# magnes.net
KiCad netlist of a schematic drawn in EAGLE
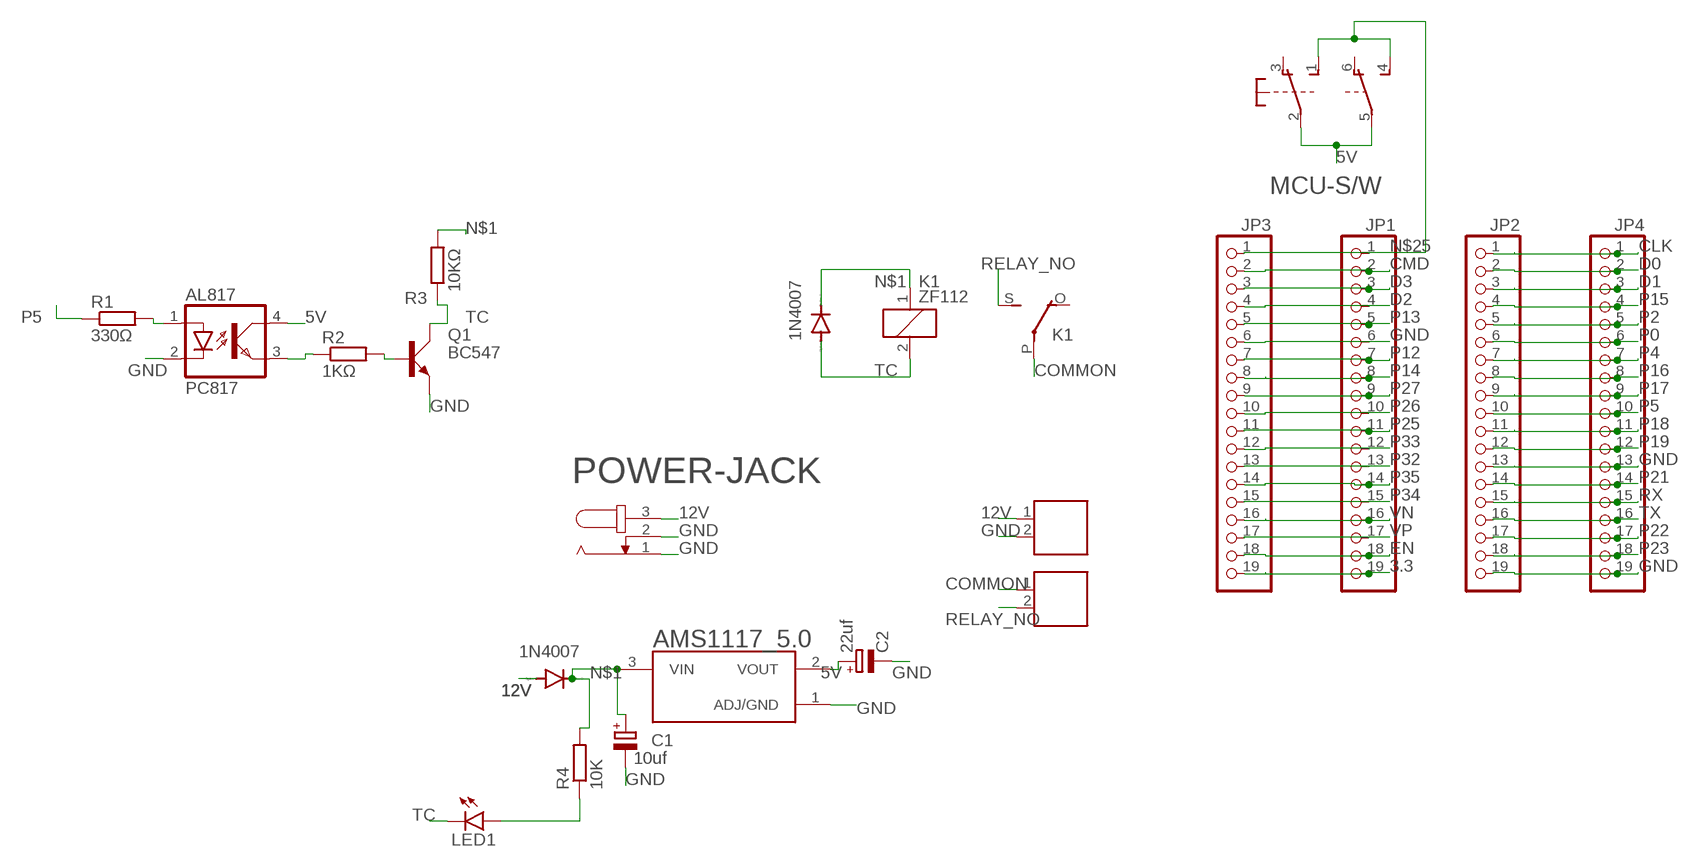
[diagram p0: schematic, sheet 1]

(export (version "E")
  (design (tool "Eeschema 10.0.6"))
  (components
    (comp (ref "1N1")
      (value "1N4007")
      (footprint "eagle-import:D-7.5")
      (libsource (lib "eagle-import") (part "DIODE-D-7.5"))
    )
    (comp (ref "1N4007")
      (value "DIODE-D-7.5")
      (footprint "eagle-import:D-7.5")
      (libsource (lib "eagle-import") (part "DIODE-D-7.5"))
    )
    (comp (ref "AL817")
      (value "PC817")
      (footprint "eagle-import:DIL04")
      (fields (field (name "MPN") "PC817X4J000F"))
      (libsource (lib "eagle-import") (part "PC817"))
    )
    (comp (ref "AMS1117_5.0")
      (value "AMS1117-3.3")
      (footprint "eagle-import:SOT229P700X180-4N")
      (fields (field (name "MF") "Advanced Monolithic Systems"))
      (libsource (lib "eagle-import") (part "AMS1117-3.3"))
    )
    (comp (ref "C1")
      (value "10uf")
      (footprint "eagle-import:E2,5-6")
      (libsource (lib "eagle-import") (part "CPOL-EUE2.5-6"))
    )
    (comp (ref "C2")
      (value "22uf")
      (footprint "eagle-import:E2,5-6")
      (libsource (lib "eagle-import") (part "CPOL-EUE2.5-6"))
    )
    (comp (ref "JP1")
      (value "PINHD-1X19")
      (footprint "eagle-import:1X19")
      (libsource (lib "eagle-import") (part "PINHD-1X19"))
    )
    (comp (ref "JP2")
      (value "PINHD-1X19")
      (footprint "eagle-import:1X19")
      (libsource (lib "eagle-import") (part "PINHD-1X19"))
    )
    (comp (ref "JP3")
      (value "PINHD-1X19")
      (footprint "eagle-import:1X19")
      (libsource (lib "eagle-import") (part "PINHD-1X19"))
    )
    (comp (ref "JP4")
      (value "PINHD-1X19")
      (footprint "eagle-import:1X19")
      (libsource (lib "eagle-import") (part "PINHD-1X19"))
    )
    (comp (ref "K1")
      (value "ZF112")
      (footprint "eagle-import:ZF112")
      (libsource (lib "eagle-import") (part "ZF112"))
    )
    (comp (ref "LED1")
      (value "LED3MM")
      (footprint "eagle-import:LED3MM")
      (libsource (lib "eagle-import") (part "LED3MM"))
    )
    (comp (ref "MCU-S/W")
      (value "9077-2")
      (footprint "eagle-import:9077-2")
      (libsource (lib "eagle-import") (part "9077-2"))
    )
    (comp (ref "PCBSCREWTERMINAL")
      (value "691131710002")
      (footprint "eagle-import:691131710002")
      (libsource (lib "eagle-import") (part "691131710002"))
    )
    (comp (ref "PCBSCREWTERMINAL1")
      (value "691131710002")
      (footprint "eagle-import:691131710002")
      (libsource (lib "eagle-import") (part "691131710002"))
    )
    (comp (ref "POWER-JACK")
      (value "JACK-PLUG1")
      (footprint "eagle-import:SPC4078")
      (libsource (lib "eagle-import") (part "JACK-PLUG1"))
    )
    (comp (ref "Q1")
      (value "BC547")
      (footprint "eagle-import:SOT54A")
      (libsource (lib "eagle-import") (part "BC547"))
    )
    (comp (ref "R1")
      (value "330Ω")
      (footprint "eagle-import:0204_7")
      (libsource (lib "eagle-import") (part "R-EU_0204/7"))
    )
    (comp (ref "R2")
      (value "1KΩ")
      (footprint "eagle-import:0204_7")
      (libsource (lib "eagle-import") (part "R-EU_0204/7"))
    )
    (comp (ref "R3")
      (value "10KΩ")
      (footprint "eagle-import:0204_7")
      (libsource (lib "eagle-import") (part "R-EU_0204/7"))
    )
    (comp (ref "R4")
      (value "10K")
      (footprint "eagle-import:0204_7")
      (libsource (lib "eagle-import") (part "R-EU_0204/7"))
    )
  )
  (nets
    (net (code "1") (name "/3.3") (class "Default")
      (node (ref "JP1") (pin "19") (pinfunction "19_19") (pintype "passive"))
      (node (ref "JP3") (pin "19") (pinfunction "19_19") (pintype "passive"))
    )
    (net (code "2") (name "/5V") (class "Default")
      (node (ref "AL817") (pin "4") (pinfunction "COL_4") (pintype "passive"))
      (node (ref "AMS1117_5.0") (pin "2") (pinfunction "VOUT_2") (pintype "output"))
      (node (ref "C2") (pin "+") (pinfunction "+_+") (pintype "passive"))
      (node (ref "MCU-S/W") (pin "2") (pinfunction "P_2") (pintype "passive"))
      (node (ref "MCU-S/W") (pin "5") (pinfunction "P_5") (pintype "passive"))
    )
    (net (code "3") (name "/12V") (class "Default")
      (node (ref "1N4007") (pin "A") (pinfunction "A_A") (pintype "passive"))
      (node (ref "PCBSCREWTERMINAL") (pin "1") (pinfunction "1_1") (pintype "passive"))
      (node (ref "POWER-JACK") (pin "3") (pinfunction "3_3") (pintype "passive"))
    )
    (net (code "4") (name "/CLK") (class "Default")
      (node (ref "JP2") (pin "1") (pinfunction "1_1") (pintype "passive"))
      (node (ref "JP4") (pin "1") (pinfunction "1_1") (pintype "passive"))
    )
    (net (code "5") (name "/CMD") (class "Default")
      (node (ref "JP1") (pin "2") (pinfunction "2_2") (pintype "passive"))
      (node (ref "JP3") (pin "2") (pinfunction "2_2") (pintype "passive"))
    )
    (net (code "6") (name "/COMMON") (class "Default")
      (node (ref "K1") (pin "P") (pinfunction "P_P") (pintype "passive"))
      (node (ref "PCBSCREWTERMINAL1") (pin "1") (pinfunction "1_1") (pintype "passive"))
    )
    (net (code "7") (name "/D0") (class "Default")
      (node (ref "JP2") (pin "2") (pinfunction "2_2") (pintype "passive"))
      (node (ref "JP4") (pin "2") (pinfunction "2_2") (pintype "passive"))
    )
    (net (code "8") (name "/D1") (class "Default")
      (node (ref "JP2") (pin "3") (pinfunction "3_3") (pintype "passive"))
      (node (ref "JP4") (pin "3") (pinfunction "3_3") (pintype "passive"))
    )
    (net (code "9") (name "/D2") (class "Default")
      (node (ref "JP1") (pin "4") (pinfunction "4_4") (pintype "passive"))
      (node (ref "JP3") (pin "4") (pinfunction "4_4") (pintype "passive"))
    )
    (net (code "10") (name "/D3") (class "Default")
      (node (ref "JP1") (pin "3") (pinfunction "3_3") (pintype "passive"))
      (node (ref "JP3") (pin "3") (pinfunction "3_3") (pintype "passive"))
    )
    (net (code "11") (name "/EN") (class "Default")
      (node (ref "JP1") (pin "18") (pinfunction "18_18") (pintype "passive"))
      (node (ref "JP3") (pin "18") (pinfunction "18_18") (pintype "passive"))
    )
    (net (code "12") (name "/GND") (class "Default")
      (node (ref "AL817") (pin "2") (pinfunction "C_2") (pintype "passive"))
      (node (ref "AMS1117_5.0") (pin "1") (pinfunction "ADJ/GND_1") (pintype "power_in"))
      (node (ref "C1") (pin "-") (pinfunction "-_-") (pintype "passive"))
      (node (ref "C2") (pin "-") (pinfunction "-_-") (pintype "passive"))
      (node (ref "JP1") (pin "6") (pinfunction "6_6") (pintype "passive"))
      (node (ref "JP2") (pin "13") (pinfunction "13_13") (pintype "passive"))
      (node (ref "JP2") (pin "19") (pinfunction "19_19") (pintype "passive"))
      (node (ref "JP3") (pin "6") (pinfunction "6_6") (pintype "passive"))
      (node (ref "JP4") (pin "13") (pinfunction "13_13") (pintype "passive"))
      (node (ref "JP4") (pin "19") (pinfunction "19_19") (pintype "passive"))
      (node (ref "PCBSCREWTERMINAL") (pin "2") (pinfunction "2_2") (pintype "passive"))
      (node (ref "POWER-JACK") (pin "1") (pinfunction "1_1") (pintype "passive"))
      (node (ref "POWER-JACK") (pin "2") (pinfunction "2_2") (pintype "passive"))
      (node (ref "Q1") (pin "E") (pinfunction "E_E") (pintype "passive"))
    )
    (net (code "13") (name "/N$1") (class "Default")
      (node (ref "1N1") (pin "C") (pinfunction "C_C") (pintype "passive"))
      (node (ref "1N4007") (pin "C") (pinfunction "C_C") (pintype "passive"))
      (node (ref "AMS1117_5.0") (pin "3") (pinfunction "VIN_3") (pintype "input"))
      (node (ref "C1") (pin "+") (pinfunction "+_+") (pintype "passive"))
      (node (ref "K1") (pin "1") (pinfunction "1_1") (pintype "passive"))
      (node (ref "R3") (pin "2") (pinfunction "2_2") (pintype "passive"))
      (node (ref "R4") (pin "2") (pinfunction "2_2") (pintype "passive"))
    )
    (net (code "14") (name "/N$25") (class "Default")
      (node (ref "JP1") (pin "1") (pinfunction "1_1") (pintype "passive"))
      (node (ref "JP3") (pin "1") (pinfunction "1_1") (pintype "passive"))
      (node (ref "MCU-S/W") (pin "1") (pinfunction "S_1") (pintype "passive"))
      (node (ref "MCU-S/W") (pin "4") (pinfunction "S_4") (pintype "passive"))
    )
    (net (code "15") (name "/P0") (class "Default")
      (node (ref "JP2") (pin "6") (pinfunction "6_6") (pintype "passive"))
      (node (ref "JP4") (pin "6") (pinfunction "6_6") (pintype "passive"))
    )
    (net (code "16") (name "/P2") (class "Default")
      (node (ref "JP2") (pin "5") (pinfunction "5_5") (pintype "passive"))
      (node (ref "JP4") (pin "5") (pinfunction "5_5") (pintype "passive"))
    )
    (net (code "17") (name "/P4") (class "Default")
      (node (ref "JP2") (pin "7") (pinfunction "7_7") (pintype "passive"))
      (node (ref "JP4") (pin "7") (pinfunction "7_7") (pintype "passive"))
    )
    (net (code "18") (name "/P5") (class "Default")
      (node (ref "JP2") (pin "10") (pinfunction "10_10") (pintype "passive"))
      (node (ref "JP4") (pin "10") (pinfunction "10_10") (pintype "passive"))
      (node (ref "R1") (pin "1") (pinfunction "1_1") (pintype "passive"))
    )
    (net (code "19") (name "/P12") (class "Default")
      (node (ref "JP1") (pin "7") (pinfunction "7_7") (pintype "passive"))
      (node (ref "JP3") (pin "7") (pinfunction "7_7") (pintype "passive"))
    )
    (net (code "20") (name "/P13") (class "Default")
      (node (ref "JP1") (pin "5") (pinfunction "5_5") (pintype "passive"))
      (node (ref "JP3") (pin "5") (pinfunction "5_5") (pintype "passive"))
    )
    (net (code "21") (name "/P14") (class "Default")
      (node (ref "JP1") (pin "8") (pinfunction "8_8") (pintype "passive"))
      (node (ref "JP3") (pin "8") (pinfunction "8_8") (pintype "passive"))
    )
    (net (code "22") (name "/P15") (class "Default")
      (node (ref "JP2") (pin "4") (pinfunction "4_4") (pintype "passive"))
      (node (ref "JP4") (pin "4") (pinfunction "4_4") (pintype "passive"))
    )
    (net (code "23") (name "/P16") (class "Default")
      (node (ref "JP2") (pin "8") (pinfunction "8_8") (pintype "passive"))
      (node (ref "JP4") (pin "8") (pinfunction "8_8") (pintype "passive"))
    )
    (net (code "24") (name "/P17") (class "Default")
      (node (ref "JP2") (pin "9") (pinfunction "9_9") (pintype "passive"))
      (node (ref "JP4") (pin "9") (pinfunction "9_9") (pintype "passive"))
    )
    (net (code "25") (name "/P18") (class "Default")
      (node (ref "JP2") (pin "11") (pinfunction "11_11") (pintype "passive"))
      (node (ref "JP4") (pin "11") (pinfunction "11_11") (pintype "passive"))
    )
    (net (code "26") (name "/P19") (class "Default")
      (node (ref "JP2") (pin "12") (pinfunction "12_12") (pintype "passive"))
      (node (ref "JP4") (pin "12") (pinfunction "12_12") (pintype "passive"))
    )
    (net (code "27") (name "/P21") (class "Default")
      (node (ref "JP2") (pin "14") (pinfunction "14_14") (pintype "passive"))
      (node (ref "JP4") (pin "14") (pinfunction "14_14") (pintype "passive"))
    )
    (net (code "28") (name "/P22") (class "Default")
      (node (ref "JP2") (pin "17") (pinfunction "17_17") (pintype "passive"))
      (node (ref "JP4") (pin "17") (pinfunction "17_17") (pintype "passive"))
    )
    (net (code "29") (name "/P23") (class "Default")
      (node (ref "JP2") (pin "18") (pinfunction "18_18") (pintype "passive"))
      (node (ref "JP4") (pin "18") (pinfunction "18_18") (pintype "passive"))
    )
    (net (code "30") (name "/P25") (class "Default")
      (node (ref "JP1") (pin "11") (pinfunction "11_11") (pintype "passive"))
      (node (ref "JP3") (pin "11") (pinfunction "11_11") (pintype "passive"))
    )
    (net (code "31") (name "/P26") (class "Default")
      (node (ref "JP1") (pin "10") (pinfunction "10_10") (pintype "passive"))
      (node (ref "JP3") (pin "10") (pinfunction "10_10") (pintype "passive"))
    )
    (net (code "32") (name "/P27") (class "Default")
      (node (ref "JP1") (pin "9") (pinfunction "9_9") (pintype "passive"))
      (node (ref "JP3") (pin "9") (pinfunction "9_9") (pintype "passive"))
    )
    (net (code "33") (name "/P32") (class "Default")
      (node (ref "JP1") (pin "13") (pinfunction "13_13") (pintype "passive"))
      (node (ref "JP3") (pin "13") (pinfunction "13_13") (pintype "passive"))
    )
    (net (code "34") (name "/P33") (class "Default")
      (node (ref "JP1") (pin "12") (pinfunction "12_12") (pintype "passive"))
      (node (ref "JP3") (pin "12") (pinfunction "12_12") (pintype "passive"))
    )
    (net (code "35") (name "/P34") (class "Default")
      (node (ref "JP1") (pin "15") (pinfunction "15_15") (pintype "passive"))
      (node (ref "JP3") (pin "15") (pinfunction "15_15") (pintype "passive"))
    )
    (net (code "36") (name "/P35") (class "Default")
      (node (ref "JP1") (pin "14") (pinfunction "14_14") (pintype "passive"))
      (node (ref "JP3") (pin "14") (pinfunction "14_14") (pintype "passive"))
    )
    (net (code "37") (name "/RELAY_NO") (class "Default")
      (node (ref "K1") (pin "S") (pinfunction "S_S") (pintype "passive"))
      (node (ref "PCBSCREWTERMINAL1") (pin "2") (pinfunction "2_2") (pintype "passive"))
    )
    (net (code "38") (name "/RX") (class "Default")
      (node (ref "JP2") (pin "15") (pinfunction "15_15") (pintype "passive"))
      (node (ref "JP4") (pin "15") (pinfunction "15_15") (pintype "passive"))
    )
    (net (code "39") (name "/TC") (class "Default")
      (node (ref "1N1") (pin "A") (pinfunction "A_A") (pintype "passive"))
      (node (ref "K1") (pin "2") (pinfunction "2_2") (pintype "passive"))
      (node (ref "LED1") (pin "K") (pinfunction "C_K") (pintype "passive"))
      (node (ref "Q1") (pin "C") (pinfunction "C_C") (pintype "passive"))
      (node (ref "R3") (pin "1") (pinfunction "1_1") (pintype "passive"))
    )
    (net (code "40") (name "/TX") (class "Default")
      (node (ref "JP2") (pin "16") (pinfunction "16_16") (pintype "passive"))
      (node (ref "JP4") (pin "16") (pinfunction "16_16") (pintype "passive"))
    )
    (net (code "41") (name "/VN") (class "Default")
      (node (ref "JP1") (pin "16") (pinfunction "16_16") (pintype "passive"))
      (node (ref "JP3") (pin "16") (pinfunction "16_16") (pintype "passive"))
    )
    (net (code "42") (name "/VP") (class "Default")
      (node (ref "JP1") (pin "17") (pinfunction "17_17") (pintype "passive"))
      (node (ref "JP3") (pin "17") (pinfunction "17_17") (pintype "passive"))
    )
    (net (code "43") (name "Net-(AL817-A)") (class "Default")
      (node (ref "AL817") (pin "1") (pinfunction "A_1") (pintype "passive"))
      (node (ref "R1") (pin "2") (pinfunction "2_2") (pintype "passive"))
    )
    (net (code "44") (name "Net-(AL817-EMIT)") (class "Default")
      (node (ref "AL817") (pin "3") (pinfunction "EMIT_3") (pintype "passive"))
      (node (ref "R2") (pin "1") (pinfunction "1_1") (pintype "passive"))
    )
    (net (code "45") (name "Net-(LED1-PadA)") (class "Default")
      (node (ref "LED1") (pin "A") (pinfunction "A_A") (pintype "passive"))
      (node (ref "R4") (pin "1") (pinfunction "1_1") (pintype "passive"))
    )
    (net (code "46") (name "Net-(Q1-PadB)") (class "Default")
      (node (ref "Q1") (pin "B") (pinfunction "B_B") (pintype "passive"))
      (node (ref "R2") (pin "2") (pinfunction "2_2") (pintype "passive"))
    )
    (net (code "47") (name "unconnected-(K1-PadO)") (class "Default")
      (node (ref "K1") (pin "O") (pinfunction "O_O") (pintype "passive"))
    )
    (net (code "48") (name "unconnected-(MCU-S/WA-O-Pad3)") (class "Default")
      (node (ref "MCU-S/W") (pin "3") (pinfunction "O_3") (pintype "passive"))
    )
    (net (code "49") (name "unconnected-(MCU-S/WB-O-Pad6)") (class "Default")
      (node (ref "MCU-S/W") (pin "6") (pinfunction "O_6") (pintype "passive"))
    )
  )
)
